# solarSwitch.net
KiCad netlist of a schematic drawn in EAGLE
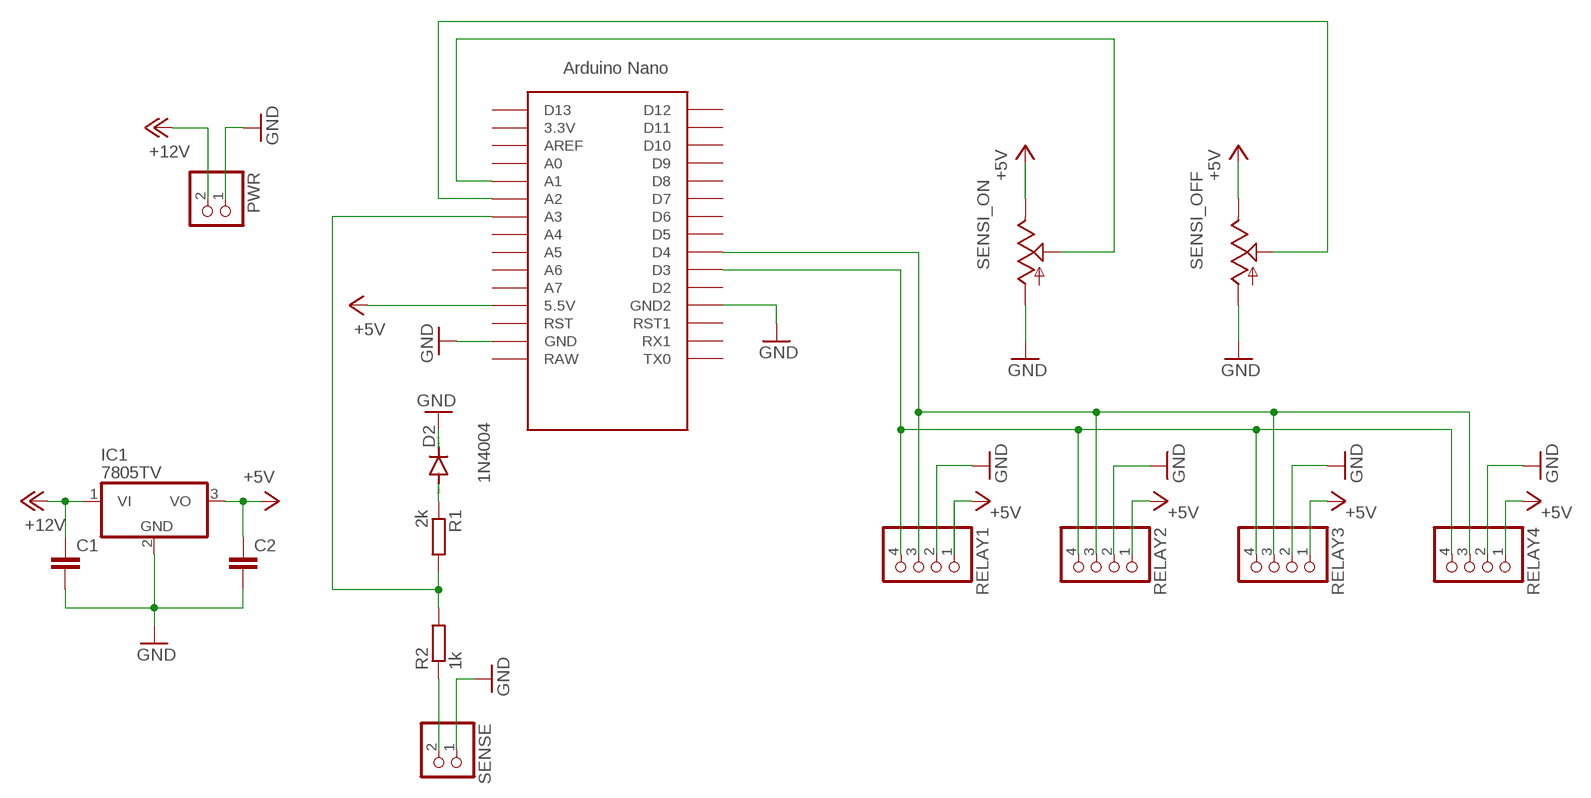
[diagram p0: schematic, sheet 1]

(export (version "E")
  (design (tool "Eeschema 10.0.6"))
  (components
    (comp (ref "C1")
      (value "C5/3")
      (footprint "eagle-import:C5B3")
      (libsource (lib "eagle-import") (part "C5/3"))
    )
    (comp (ref "C2")
      (value "C5/3")
      (footprint "eagle-import:C5B3")
      (libsource (lib "eagle-import") (part "C5/3"))
    )
    (comp (ref "D2")
      (value "1N4004")
      (footprint "eagle-import:DO41-10")
      (libsource (lib "eagle-import") (part "1N4004"))
    )
    (comp (ref "IC1")
      (value "7805TV")
      (footprint "eagle-import:TO220V")
      (libsource (lib "eagle-import") (part "78TV05"))
    )
    (comp (ref "PWR")
      (value "PINHD-1X2")
      (footprint "eagle-import:1X02")
      (libsource (lib "eagle-import") (part "PINHD-1X2"))
    )
    (comp (ref "R1")
      (value "2k")
      (footprint "eagle-import:0204_7")
      (libsource (lib "eagle-import") (part "R-EU_0204/7"))
    )
    (comp (ref "R2")
      (value "1k")
      (footprint "eagle-import:0204_7")
      (libsource (lib "eagle-import") (part "R-EU_0204/7"))
    )
    (comp (ref "RELAY1")
      (value "PINHD-1X4")
      (footprint "eagle-import:1X04")
      (libsource (lib "eagle-import") (part "PINHD-1X4"))
    )
    (comp (ref "RELAY2")
      (value "PINHD-1X4")
      (footprint "eagle-import:1X04")
      (libsource (lib "eagle-import") (part "PINHD-1X4"))
    )
    (comp (ref "RELAY3")
      (value "PINHD-1X4")
      (footprint "eagle-import:1X04")
      (libsource (lib "eagle-import") (part "PINHD-1X4"))
    )
    (comp (ref "RELAY4")
      (value "PINHD-1X4")
      (footprint "eagle-import:1X04")
      (libsource (lib "eagle-import") (part "PINHD-1X4"))
    )
    (comp (ref "SENSE")
      (value "PINHD-1X2")
      (footprint "eagle-import:1X02")
      (libsource (lib "eagle-import") (part "PINHD-1X2"))
    )
    (comp (ref "SENSI_OFF")
      (value "TRIM_US-B25P")
      (footprint "eagle-import:B25P")
      (libsource (lib "eagle-import") (part "TRIM_US-B25P"))
    )
    (comp (ref "SENSI_ON")
      (value "TRIM_US-B25P")
      (footprint "eagle-import:B25P")
      (libsource (lib "eagle-import") (part "TRIM_US-B25P"))
    )
    (comp (ref "U$1")
      (value "NANO")
      (footprint "eagle-import:NANO")
      (libsource (lib "eagle-import") (part "NANO"))
    )
  )
  (nets
    (net (code "1") (name "+5V") (class "Default")
      (node (ref "C2") (pin "1") (pinfunction "1_1") (pintype "passive"))
      (node (ref "IC1") (pin "3") (pinfunction "VO_3") (pintype "passive"))
      (node (ref "RELAY1") (pin "1") (pinfunction "1_1") (pintype "passive"))
      (node (ref "RELAY2") (pin "1") (pinfunction "1_1") (pintype "passive"))
      (node (ref "RELAY3") (pin "1") (pinfunction "1_1") (pintype "passive"))
      (node (ref "RELAY4") (pin "1") (pinfunction "1_1") (pintype "passive"))
      (node (ref "SENSI_OFF") (pin "E") (pinfunction "E_E") (pintype "passive"))
      (node (ref "SENSI_ON") (pin "E") (pinfunction "E_E") (pintype "passive"))
      (node (ref "U$1") (pin "5V") (pinfunction "5.5V_5V") (pintype "bidirectional"))
    )
    (net (code "2") (name "+12V") (class "Default")
      (node (ref "C1") (pin "1") (pinfunction "1_1") (pintype "passive"))
      (node (ref "IC1") (pin "1") (pinfunction "VI_1") (pintype "input"))
      (node (ref "PWR") (pin "2") (pinfunction "2_2") (pintype "passive"))
    )
    (net (code "3") (name "GND") (class "Default")
      (node (ref "C1") (pin "2") (pinfunction "2_2") (pintype "passive"))
      (node (ref "C2") (pin "2") (pinfunction "2_2") (pintype "passive"))
      (node (ref "D2") (pin "C") (pinfunction "C_C") (pintype "passive"))
      (node (ref "IC1") (pin "2") (pinfunction "GND_2") (pintype "passive"))
      (node (ref "PWR") (pin "1") (pinfunction "1_1") (pintype "passive"))
      (node (ref "RELAY1") (pin "2") (pinfunction "2_2") (pintype "passive"))
      (node (ref "RELAY2") (pin "2") (pinfunction "2_2") (pintype "passive"))
      (node (ref "RELAY3") (pin "2") (pinfunction "2_2") (pintype "passive"))
      (node (ref "RELAY4") (pin "2") (pinfunction "2_2") (pintype "passive"))
      (node (ref "SENSE") (pin "1") (pinfunction "1_1") (pintype "passive"))
      (node (ref "SENSI_OFF") (pin "A") (pinfunction "A_A") (pintype "passive"))
      (node (ref "SENSI_ON") (pin "A") (pinfunction "A_A") (pintype "passive"))
      (node (ref "U$1") (pin "GND") (pinfunction "GND_GND") (pintype "bidirectional"))
      (node (ref "U$1") (pin "GND1") (pinfunction "GND2_GND1") (pintype "bidirectional"))
    )
    (net (code "4") (name "Net-(D2-PadA)") (class "Default")
      (node (ref "D2") (pin "A") (pinfunction "A_A") (pintype "passive"))
      (node (ref "R1") (pin "1") (pinfunction "1_1") (pintype "passive"))
    )
    (net (code "5") (name "Net-(R1-Pad2)") (class "Default")
      (node (ref "R1") (pin "2") (pinfunction "2_2") (pintype "passive"))
      (node (ref "R2") (pin "2") (pinfunction "2_2") (pintype "passive"))
      (node (ref "U$1") (pin "A3") (pinfunction "A3_A3") (pintype "bidirectional"))
    )
    (net (code "6") (name "Net-(R2-Pad1)") (class "Default")
      (node (ref "R2") (pin "1") (pinfunction "1_1") (pintype "passive"))
      (node (ref "SENSE") (pin "2") (pinfunction "2_2") (pintype "passive"))
    )
    (net (code "7") (name "Net-(RELAY1-Pad3)") (class "Default")
      (node (ref "RELAY1") (pin "3") (pinfunction "3_3") (pintype "passive"))
      (node (ref "RELAY2") (pin "3") (pinfunction "3_3") (pintype "passive"))
      (node (ref "RELAY3") (pin "3") (pinfunction "3_3") (pintype "passive"))
      (node (ref "RELAY4") (pin "3") (pinfunction "3_3") (pintype "passive"))
      (node (ref "U$1") (pin "D4") (pinfunction "D4_D4") (pintype "bidirectional"))
    )
    (net (code "8") (name "Net-(RELAY1-Pad4)") (class "Default")
      (node (ref "RELAY1") (pin "4") (pinfunction "4_4") (pintype "passive"))
      (node (ref "RELAY2") (pin "4") (pinfunction "4_4") (pintype "passive"))
      (node (ref "RELAY3") (pin "4") (pinfunction "4_4") (pintype "passive"))
      (node (ref "RELAY4") (pin "4") (pinfunction "4_4") (pintype "passive"))
      (node (ref "U$1") (pin "D3") (pinfunction "D3_D3") (pintype "bidirectional"))
    )
    (net (code "9") (name "Net-(SENSI_OFF-PadS)") (class "Default")
      (node (ref "SENSI_OFF") (pin "S") (pinfunction "S_S") (pintype "passive"))
      (node (ref "U$1") (pin "A2") (pinfunction "A2_A2") (pintype "bidirectional"))
    )
    (net (code "10") (name "Net-(SENSI_ON-PadS)") (class "Default")
      (node (ref "SENSI_ON") (pin "S") (pinfunction "S_S") (pintype "passive"))
      (node (ref "U$1") (pin "A1") (pinfunction "A1_A1") (pintype "bidirectional"))
    )
    (net (code "11") (name "unconnected-(U$1-Pad3.3V)") (class "Default")
      (node (ref "U$1") (pin "3.3V") (pinfunction "3.3V_3.3V") (pintype "bidirectional"))
    )
    (net (code "12") (name "unconnected-(U$1-PadA0)") (class "Default")
      (node (ref "U$1") (pin "A0") (pinfunction "A0_A0") (pintype "bidirectional"))
    )
    (net (code "13") (name "unconnected-(U$1-PadA4)") (class "Default")
      (node (ref "U$1") (pin "A4") (pinfunction "A4_A4") (pintype "bidirectional"))
    )
    (net (code "14") (name "unconnected-(U$1-PadA5)") (class "Default")
      (node (ref "U$1") (pin "A5") (pinfunction "A5_A5") (pintype "bidirectional"))
    )
    (net (code "15") (name "unconnected-(U$1-PadA6)") (class "Default")
      (node (ref "U$1") (pin "A6") (pinfunction "A6_A6") (pintype "bidirectional"))
    )
    (net (code "16") (name "unconnected-(U$1-PadA7)") (class "Default")
      (node (ref "U$1") (pin "A7") (pinfunction "A7_A7") (pintype "bidirectional"))
    )
    (net (code "17") (name "unconnected-(U$1-PadAREF)") (class "Default")
      (node (ref "U$1") (pin "AREF") (pinfunction "AREF_AREF") (pintype "bidirectional"))
    )
    (net (code "18") (name "unconnected-(U$1-PadD2)") (class "Default")
      (node (ref "U$1") (pin "D2") (pinfunction "D2_D2") (pintype "bidirectional"))
    )
    (net (code "19") (name "unconnected-(U$1-PadD5)") (class "Default")
      (node (ref "U$1") (pin "D5") (pinfunction "D5_D5") (pintype "bidirectional"))
    )
    (net (code "20") (name "unconnected-(U$1-PadD6)") (class "Default")
      (node (ref "U$1") (pin "D6") (pinfunction "D6_D6") (pintype "bidirectional"))
    )
    (net (code "21") (name "unconnected-(U$1-PadD7)") (class "Default")
      (node (ref "U$1") (pin "D7") (pinfunction "D7_D7") (pintype "bidirectional"))
    )
    (net (code "22") (name "unconnected-(U$1-PadD8)") (class "Default")
      (node (ref "U$1") (pin "D8") (pinfunction "D8_D8") (pintype "bidirectional"))
    )
    (net (code "23") (name "unconnected-(U$1-PadD9)") (class "Default")
      (node (ref "U$1") (pin "D9") (pinfunction "D9_D9") (pintype "bidirectional"))
    )
    (net (code "24") (name "unconnected-(U$1-PadD10)") (class "Default")
      (node (ref "U$1") (pin "D10") (pinfunction "D10_D10") (pintype "bidirectional"))
    )
    (net (code "25") (name "unconnected-(U$1-PadD11)") (class "Default")
      (node (ref "U$1") (pin "D11") (pinfunction "D11_D11") (pintype "bidirectional"))
    )
    (net (code "26") (name "unconnected-(U$1-PadD12)") (class "Default")
      (node (ref "U$1") (pin "D12") (pinfunction "D12_D12") (pintype "bidirectional"))
    )
    (net (code "27") (name "unconnected-(U$1-PadD13)") (class "Default")
      (node (ref "U$1") (pin "D13") (pinfunction "D13_D13") (pintype "bidirectional"))
    )
    (net (code "28") (name "unconnected-(U$1-PadICSP1)") (class "Default")
      (node (ref "U$1") (pin "ICSP1") (pinfunction "ICSP1_ICSP1") (pintype "bidirectional"))
    )
    (net (code "29") (name "unconnected-(U$1-PadICSP2)") (class "Default")
      (node (ref "U$1") (pin "ICSP2") (pinfunction "ICSP2_ICSP2") (pintype "bidirectional"))
    )
    (net (code "30") (name "unconnected-(U$1-PadICSP3)") (class "Default")
      (node (ref "U$1") (pin "ICSP3") (pinfunction "ICSP3_ICSP3") (pintype "bidirectional"))
    )
    (net (code "31") (name "unconnected-(U$1-PadICSP4)") (class "Default")
      (node (ref "U$1") (pin "ICSP4") (pinfunction "ICSP4_ICSP4") (pintype "bidirectional"))
    )
    (net (code "32") (name "unconnected-(U$1-PadICSP5)") (class "Default")
      (node (ref "U$1") (pin "ICSP5") (pinfunction "ICSP5_ICSP5") (pintype "bidirectional"))
    )
    (net (code "33") (name "unconnected-(U$1-PadICSP6)") (class "Default")
      (node (ref "U$1") (pin "ICSP6") (pinfunction "ICSP6_ICSP6") (pintype "bidirectional"))
    )
    (net (code "34") (name "unconnected-(U$1-PadRAW)") (class "Default")
      (node (ref "U$1") (pin "RAW") (pinfunction "RAW_RAW") (pintype "bidirectional"))
    )
    (net (code "35") (name "unconnected-(U$1-PadRST)") (class "Default")
      (node (ref "U$1") (pin "RST") (pinfunction "RST_RST") (pintype "bidirectional"))
    )
    (net (code "36") (name "unconnected-(U$1-PadRST1)") (class "Default")
      (node (ref "U$1") (pin "RST1") (pinfunction "RST1_RST1") (pintype "bidirectional"))
    )
    (net (code "37") (name "unconnected-(U$1-PadRX1)") (class "Default")
      (node (ref "U$1") (pin "RX1") (pinfunction "RX1_RX1") (pintype "bidirectional"))
    )
    (net (code "38") (name "unconnected-(U$1-PadTX0)") (class "Default")
      (node (ref "U$1") (pin "TX0") (pinfunction "TX0_TX0") (pintype "bidirectional"))
    )
  )
)
